# NXMaus.net
KiCad netlist of a schematic drawn in EAGLE
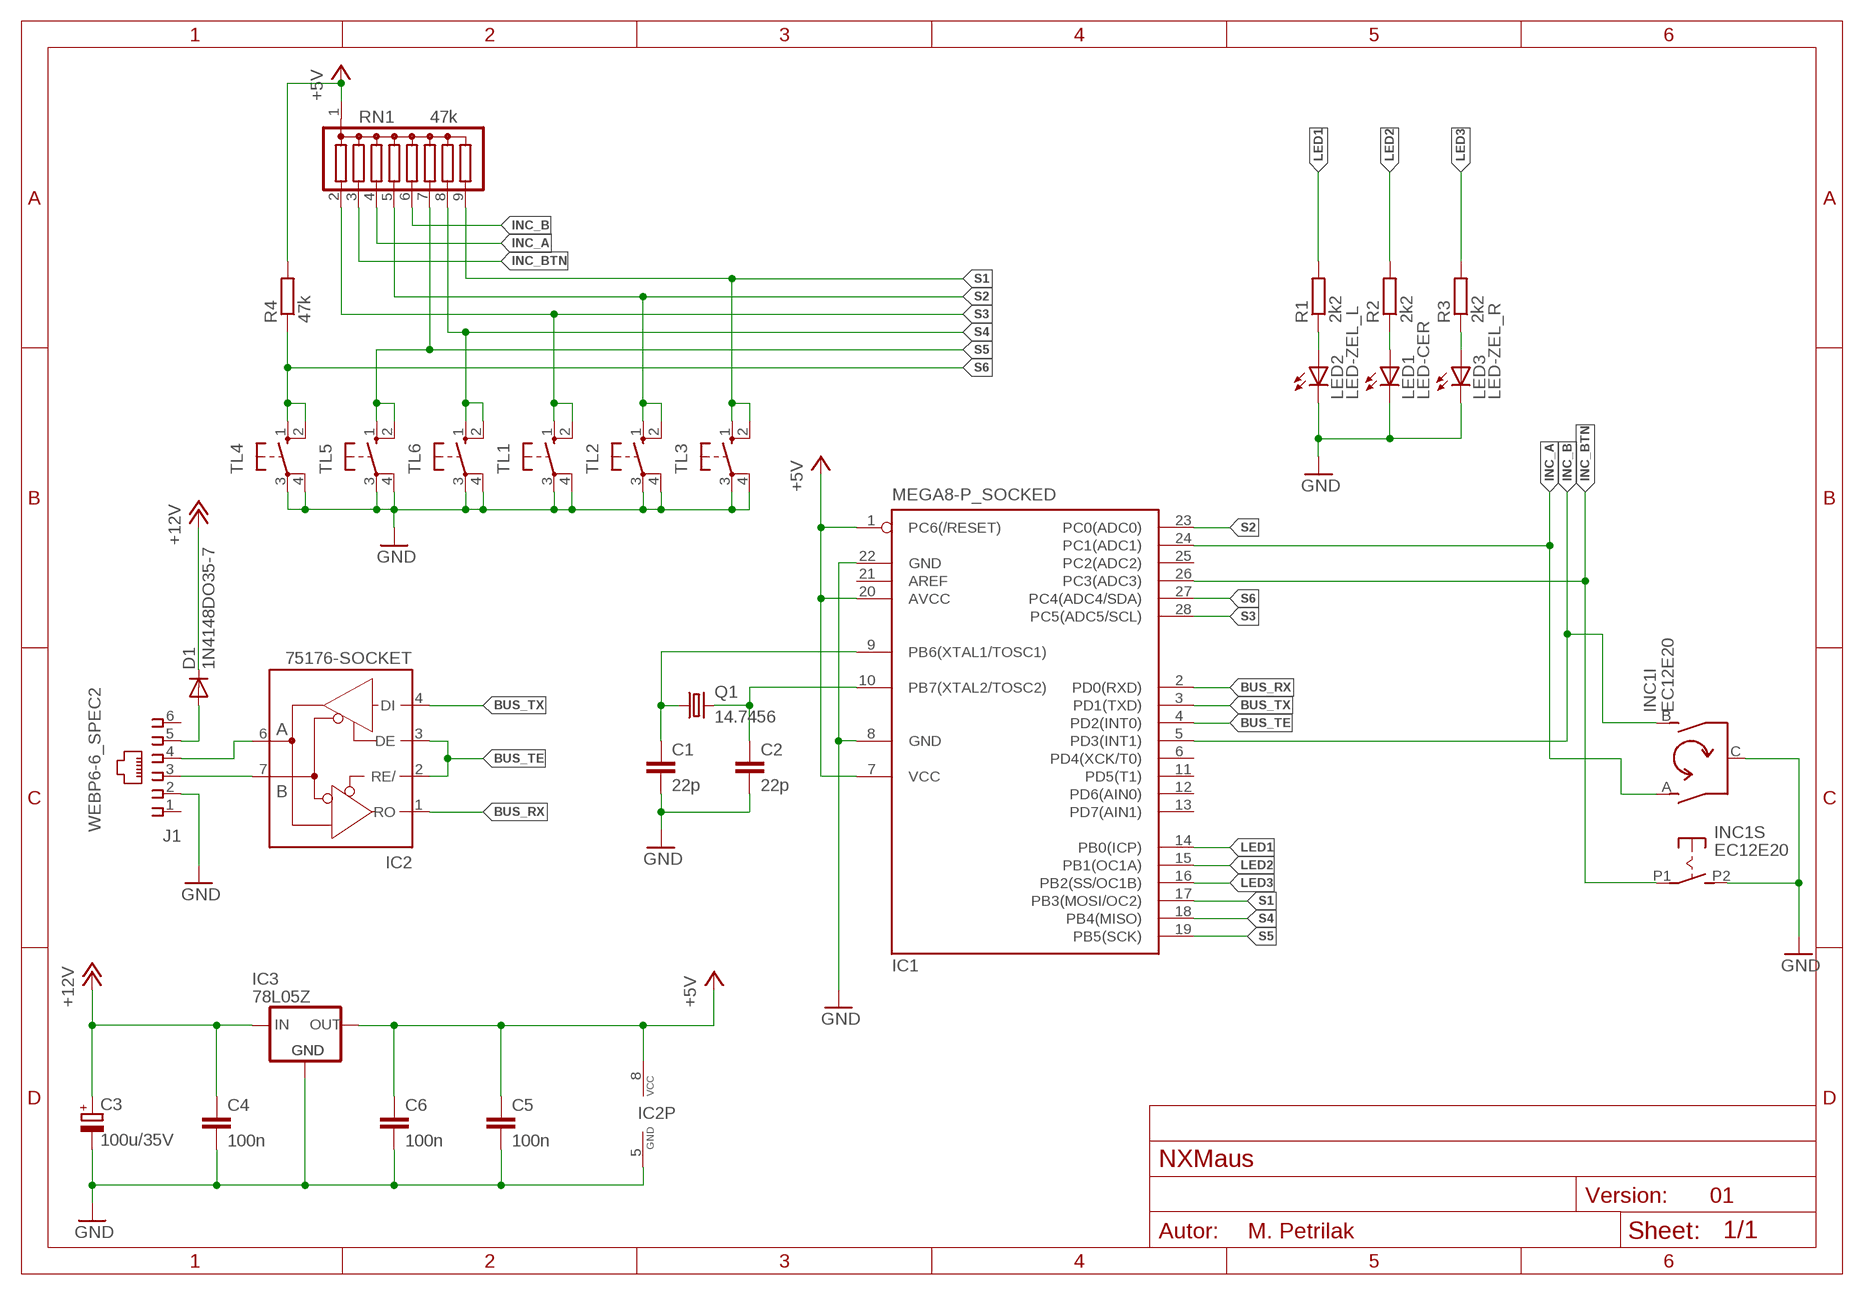
[diagram p0: schematic, sheet 1]

(export (version "E")
  (design (tool "Eeschema 10.0.6"))
  (components
    (comp (ref "C1")
      (value "22p")
      (footprint "eagle-import:C025_050-025X075")
      (libsource (lib "eagle-import") (part "C-EU025_050-025X075"))
    )
    (comp (ref "C2")
      (value "22p")
      (footprint "eagle-import:C025_050-025X075")
      (libsource (lib "eagle-import") (part "C-EU025_050-025X075"))
    )
    (comp (ref "C3")
      (value "100u/35V")
      (footprint "eagle-import:E2,5-6")
      (libsource (lib "eagle-import") (part "CPOL-EUE2.5-6"))
    )
    (comp (ref "C4")
      (value "100n")
      (footprint "eagle-import:C025_050-025X075")
      (libsource (lib "eagle-import") (part "C-EU025_050-025X075"))
    )
    (comp (ref "C5")
      (value "100n")
      (footprint "eagle-import:C025_050-025X075")
      (libsource (lib "eagle-import") (part "C-EU025_050-025X075"))
    )
    (comp (ref "C6")
      (value "100n")
      (footprint "eagle-import:C025_050-025X075")
      (libsource (lib "eagle-import") (part "C-EU025_050-025X075"))
    )
    (comp (ref "D1")
      (value "1N4148DO35-7")
      (footprint "eagle-import:DO35-7")
      (libsource (lib "eagle-import") (part "1N4148DO35-7"))
    )
    (comp (ref "IC1")
      (value "MEGA8-P_SOCKED")
      (footprint "eagle-import:SOKL-28U")
      (libsource (lib "eagle-import") (part "MEGA8-P_SOCKED"))
    )
    (comp (ref "IC2")
      (value "75176-SOCKET")
      (footprint "eagle-import:SOCKET-08")
      (libsource (lib "eagle-import") (part "75176-SOCKET"))
    )
    (comp (ref "IC3")
      (value "78L05Z")
      (footprint "eagle-import:TO92")
      (libsource (lib "eagle-import") (part "78ZL05"))
    )
    (comp (ref "INC1")
      (value "EC12E20")
      (footprint "eagle-import:EC12E20")
      (libsource (lib "eagle-import") (part "EC12E20"))
    )
    (comp (ref "J1")
      (value "WEBP6-6_SPEC2")
      (footprint "eagle-import:WEBP6-6_SPEC2")
      (libsource (lib "eagle-import") (part "WEBP6-6_SPEC2"))
    )
    (comp (ref "LED1")
      (value "LED-CER")
      (footprint "eagle-import:LED3MM")
      (libsource (lib "eagle-import") (part "LED3MM"))
    )
    (comp (ref "LED2")
      (value "LED-ZEL_L")
      (footprint "eagle-import:LED3MM")
      (libsource (lib "eagle-import") (part "LED3MM"))
    )
    (comp (ref "LED3")
      (value "LED-ZEL_R")
      (footprint "eagle-import:LED3MM")
      (libsource (lib "eagle-import") (part "LED3MM"))
    )
    (comp (ref "Q1")
      (value "14.7456")
      (footprint "eagle-import:HC49U70")
      (libsource (lib "eagle-import") (part "XTAL"))
    )
    (comp (ref "R1")
      (value "2k2")
      (footprint "eagle-import:0207_10")
      (libsource (lib "eagle-import") (part "R-EU_0207/10"))
    )
    (comp (ref "R2")
      (value "2k2")
      (footprint "eagle-import:0207_10")
      (libsource (lib "eagle-import") (part "R-EU_0207/10"))
    )
    (comp (ref "R3")
      (value "2k2")
      (footprint "eagle-import:0207_10")
      (libsource (lib "eagle-import") (part "R-EU_0207/10"))
    )
    (comp (ref "R4")
      (value "47k")
      (footprint "eagle-import:R1206")
      (libsource (lib "eagle-import") (part "R-EU_R1206"))
    )
    (comp (ref "RN1")
      (value "47k")
      (footprint "eagle-import:SIL9")
      (libsource (lib "eagle-import") (part "G08R"))
    )
    (comp (ref "TL1")
      (value "10-XX")
      (footprint "eagle-import:B3F-10XX")
      (libsource (lib "eagle-import") (part "10-XX"))
    )
    (comp (ref "TL2")
      (value "10-XX")
      (footprint "eagle-import:B3F-10XX")
      (libsource (lib "eagle-import") (part "10-XX"))
    )
    (comp (ref "TL3")
      (value "10-XX")
      (footprint "eagle-import:B3F-10XX")
      (libsource (lib "eagle-import") (part "10-XX"))
    )
    (comp (ref "TL4")
      (value "10-XX")
      (footprint "eagle-import:B3F-10XX")
      (libsource (lib "eagle-import") (part "10-XX"))
    )
    (comp (ref "TL5")
      (value "10-XX")
      (footprint "eagle-import:B3F-10XX")
      (libsource (lib "eagle-import") (part "10-XX"))
    )
    (comp (ref "TL6")
      (value "10-XX")
      (footprint "eagle-import:B3F-10XX")
      (libsource (lib "eagle-import") (part "10-XX"))
    )
  )
  (nets
    (net (code "1") (name "+5V") (class "Default")
      (node (ref "C5") (pin "1") (pinfunction "1_1") (pintype "passive"))
      (node (ref "C6") (pin "1") (pinfunction "1_1") (pintype "passive"))
      (node (ref "IC1") (pin "1") (pinfunction "PC6(/RESET)_1") (pintype "bidirectional"))
      (node (ref "IC1") (pin "20") (pinfunction "AVCC_20") (pintype "power_in"))
      (node (ref "IC1") (pin "7") (pinfunction "VCC_7") (pintype "power_in"))
      (node (ref "IC2") (pin "8") (pinfunction "VCC_8") (pintype "power_in"))
      (node (ref "IC3") (pin "1") (pinfunction "VO_1") (pintype "passive"))
      (node (ref "R4") (pin "2") (pinfunction "2_2") (pintype "passive"))
      (node (ref "RN1") (pin "1") (pinfunction "1_1") (pintype "passive"))
    )
    (net (code "2") (name "+12V") (class "Default")
      (node (ref "C3") (pin "+") (pinfunction "+_+") (pintype "passive"))
      (node (ref "C4") (pin "1") (pinfunction "1_1") (pintype "passive"))
      (node (ref "D1") (pin "C") (pinfunction "C_C") (pintype "passive"))
      (node (ref "IC3") (pin "3") (pinfunction "VI_3") (pintype "input"))
    )
    (net (code "3") (name "BUS_RX") (class "Default")
      (node (ref "IC1") (pin "2") (pinfunction "PD0(RXD)_2") (pintype "bidirectional"))
      (node (ref "IC2") (pin "1") (pinfunction "RO_1") (pintype "output"))
    )
    (net (code "4") (name "BUS_TE") (class "Default")
      (node (ref "IC1") (pin "4") (pinfunction "PD2(INT0)_4") (pintype "bidirectional"))
      (node (ref "IC2") (pin "2") (pinfunction "RE/_2") (pintype "input"))
      (node (ref "IC2") (pin "3") (pinfunction "DE_3") (pintype "input"))
    )
    (net (code "5") (name "BUS_TX") (class "Default")
      (node (ref "IC1") (pin "3") (pinfunction "PD1(TXD)_3") (pintype "bidirectional"))
      (node (ref "IC2") (pin "4") (pinfunction "DI_4") (pintype "input"))
    )
    (net (code "6") (name "GND") (class "Default")
      (node (ref "C1") (pin "2") (pinfunction "2_2") (pintype "passive"))
      (node (ref "C1") (pin "3") (pinfunction "2_3") (pintype "passive"))
      (node (ref "C2") (pin "2") (pinfunction "2_2") (pintype "passive"))
      (node (ref "C2") (pin "3") (pinfunction "2_3") (pintype "passive"))
      (node (ref "C3") (pin "-") (pinfunction "-_-") (pintype "passive"))
      (node (ref "C4") (pin "2") (pinfunction "2_2") (pintype "passive"))
      (node (ref "C4") (pin "3") (pinfunction "2_3") (pintype "passive"))
      (node (ref "C5") (pin "2") (pinfunction "2_2") (pintype "passive"))
      (node (ref "C5") (pin "3") (pinfunction "2_3") (pintype "passive"))
      (node (ref "C6") (pin "2") (pinfunction "2_2") (pintype "passive"))
      (node (ref "C6") (pin "3") (pinfunction "2_3") (pintype "passive"))
      (node (ref "IC1") (pin "22") (pinfunction "GND_22") (pintype "power_in"))
      (node (ref "IC1") (pin "8") (pinfunction "GND_8") (pintype "power_in"))
      (node (ref "IC2") (pin "5") (pinfunction "GND_5") (pintype "power_in"))
      (node (ref "IC3") (pin "2") (pinfunction "GND_2") (pintype "passive"))
      (node (ref "INC1") (pin "C") (pinfunction "C_C") (pintype "passive"))
      (node (ref "INC1") (pin "P2") (pinfunction "S_P2") (pintype "passive"))
      (node (ref "J1") (pin "2") (pinfunction "2_2") (pintype "passive"))
      (node (ref "LED1") (pin "K") (pinfunction "C_K") (pintype "passive"))
      (node (ref "LED2") (pin "K") (pinfunction "C_K") (pintype "passive"))
      (node (ref "LED3") (pin "K") (pinfunction "C_K") (pintype "passive"))
      (node (ref "TL1") (pin "3") (pinfunction "P_3") (pintype "passive"))
      (node (ref "TL1") (pin "4") (pinfunction "P1_4") (pintype "passive"))
      (node (ref "TL2") (pin "3") (pinfunction "P_3") (pintype "passive"))
      (node (ref "TL2") (pin "4") (pinfunction "P1_4") (pintype "passive"))
      (node (ref "TL3") (pin "3") (pinfunction "P_3") (pintype "passive"))
      (node (ref "TL3") (pin "4") (pinfunction "P1_4") (pintype "passive"))
      (node (ref "TL4") (pin "3") (pinfunction "P_3") (pintype "passive"))
      (node (ref "TL4") (pin "4") (pinfunction "P1_4") (pintype "passive"))
      (node (ref "TL5") (pin "3") (pinfunction "P_3") (pintype "passive"))
      (node (ref "TL5") (pin "4") (pinfunction "P1_4") (pintype "passive"))
      (node (ref "TL6") (pin "3") (pinfunction "P_3") (pintype "passive"))
      (node (ref "TL6") (pin "4") (pinfunction "P1_4") (pintype "passive"))
    )
    (net (code "7") (name "INC_A") (class "Default")
      (node (ref "IC1") (pin "24") (pinfunction "PC1(ADC1)_24") (pintype "bidirectional"))
      (node (ref "INC1") (pin "A") (pinfunction "A_A") (pintype "passive"))
      (node (ref "RN1") (pin "4") (pinfunction "4_4") (pintype "passive"))
    )
    (net (code "8") (name "INC_B") (class "Default")
      (node (ref "IC1") (pin "5") (pinfunction "PD3(INT1)_5") (pintype "bidirectional"))
      (node (ref "INC1") (pin "B") (pinfunction "B_B") (pintype "passive"))
      (node (ref "RN1") (pin "6") (pinfunction "6_6") (pintype "passive"))
    )
    (net (code "9") (name "INC_BTN") (class "Default")
      (node (ref "IC1") (pin "26") (pinfunction "PC3(ADC3)_26") (pintype "bidirectional"))
      (node (ref "INC1") (pin "P1") (pinfunction "P_P1") (pintype "passive"))
      (node (ref "RN1") (pin "3") (pinfunction "3_3") (pintype "passive"))
    )
    (net (code "10") (name "LED1") (class "Default")
      (node (ref "IC1") (pin "14") (pinfunction "PB0(ICP)_14") (pintype "bidirectional"))
      (node (ref "R1") (pin "2") (pinfunction "2_2") (pintype "passive"))
    )
    (net (code "11") (name "LED2") (class "Default")
      (node (ref "IC1") (pin "15") (pinfunction "PB1(OC1A)_15") (pintype "bidirectional"))
      (node (ref "R2") (pin "2") (pinfunction "2_2") (pintype "passive"))
    )
    (net (code "12") (name "LED3") (class "Default")
      (node (ref "IC1") (pin "16") (pinfunction "PB2(SS/OC1B)_16") (pintype "bidirectional"))
      (node (ref "R3") (pin "2") (pinfunction "2_2") (pintype "passive"))
    )
    (net (code "13") (name "Net-(D1-PadA)") (class "Default")
      (node (ref "D1") (pin "A") (pinfunction "A_A") (pintype "passive"))
      (node (ref "J1") (pin "5") (pinfunction "5_5") (pintype "passive"))
    )
    (net (code "14") (name "Net-(IC1-PB6(XTAL1{slash}TOSC1))") (class "Default")
      (node (ref "C1") (pin "1") (pinfunction "1_1") (pintype "passive"))
      (node (ref "IC1") (pin "9") (pinfunction "PB6(XTAL1/TOSC1)_9") (pintype "bidirectional"))
      (node (ref "Q1") (pin "1") (pinfunction "1_1") (pintype "passive"))
    )
    (net (code "15") (name "Net-(IC1-PB7(XTAL2{slash}TOSC2))") (class "Default")
      (node (ref "C2") (pin "1") (pinfunction "1_1") (pintype "passive"))
      (node (ref "IC1") (pin "10") (pinfunction "PB7(XTAL2/TOSC2)_10") (pintype "bidirectional"))
      (node (ref "Q1") (pin "2") (pinfunction "2_2") (pintype "passive"))
    )
    (net (code "16") (name "Net-(IC2A-A)") (class "Default")
      (node (ref "IC2") (pin "6") (pinfunction "A_6") (pintype "passive"))
      (node (ref "J1") (pin "4") (pinfunction "4_4") (pintype "passive"))
    )
    (net (code "17") (name "Net-(IC2A-B)") (class "Default")
      (node (ref "IC2") (pin "7") (pinfunction "B_7") (pintype "passive"))
      (node (ref "J1") (pin "3") (pinfunction "3_3") (pintype "passive"))
    )
    (net (code "18") (name "Net-(LED1-PadA)") (class "Default")
      (node (ref "LED1") (pin "A") (pinfunction "A_A") (pintype "passive"))
      (node (ref "R2") (pin "1") (pinfunction "1_1") (pintype "passive"))
    )
    (net (code "19") (name "Net-(LED2-PadA)") (class "Default")
      (node (ref "LED2") (pin "A") (pinfunction "A_A") (pintype "passive"))
      (node (ref "R1") (pin "1") (pinfunction "1_1") (pintype "passive"))
    )
    (net (code "20") (name "Net-(LED3-PadA)") (class "Default")
      (node (ref "LED3") (pin "A") (pinfunction "A_A") (pintype "passive"))
      (node (ref "R3") (pin "1") (pinfunction "1_1") (pintype "passive"))
    )
    (net (code "21") (name "S1") (class "Default")
      (node (ref "IC1") (pin "17") (pinfunction "PB3(MOSI/OC2)_17") (pintype "bidirectional"))
      (node (ref "RN1") (pin "9") (pinfunction "9_9") (pintype "passive"))
      (node (ref "TL3") (pin "1") (pinfunction "S_1") (pintype "passive"))
      (node (ref "TL3") (pin "2") (pinfunction "S1_2") (pintype "passive"))
    )
    (net (code "22") (name "S2") (class "Default")
      (node (ref "IC1") (pin "23") (pinfunction "PC0(ADC0)_23") (pintype "bidirectional"))
      (node (ref "RN1") (pin "5") (pinfunction "5_5") (pintype "passive"))
      (node (ref "TL2") (pin "1") (pinfunction "S_1") (pintype "passive"))
      (node (ref "TL2") (pin "2") (pinfunction "S1_2") (pintype "passive"))
    )
    (net (code "23") (name "S3") (class "Default")
      (node (ref "IC1") (pin "28") (pinfunction "PC5(ADC5/SCL)_28") (pintype "bidirectional"))
      (node (ref "RN1") (pin "2") (pinfunction "2_2") (pintype "passive"))
      (node (ref "TL1") (pin "1") (pinfunction "S_1") (pintype "passive"))
      (node (ref "TL1") (pin "2") (pinfunction "S1_2") (pintype "passive"))
    )
    (net (code "24") (name "S4") (class "Default")
      (node (ref "IC1") (pin "18") (pinfunction "PB4(MISO)_18") (pintype "bidirectional"))
      (node (ref "RN1") (pin "8") (pinfunction "8_8") (pintype "passive"))
      (node (ref "TL6") (pin "1") (pinfunction "S_1") (pintype "passive"))
      (node (ref "TL6") (pin "2") (pinfunction "S1_2") (pintype "passive"))
    )
    (net (code "25") (name "S5") (class "Default")
      (node (ref "IC1") (pin "19") (pinfunction "PB5(SCK)_19") (pintype "bidirectional"))
      (node (ref "RN1") (pin "7") (pinfunction "7_7") (pintype "passive"))
      (node (ref "TL5") (pin "1") (pinfunction "S_1") (pintype "passive"))
      (node (ref "TL5") (pin "2") (pinfunction "S1_2") (pintype "passive"))
    )
    (net (code "26") (name "S6") (class "Default")
      (node (ref "IC1") (pin "27") (pinfunction "PC4(ADC4/SDA)_27") (pintype "bidirectional"))
      (node (ref "R4") (pin "1") (pinfunction "1_1") (pintype "passive"))
      (node (ref "TL4") (pin "1") (pinfunction "S_1") (pintype "passive"))
      (node (ref "TL4") (pin "2") (pinfunction "S1_2") (pintype "passive"))
    )
    (net (code "27") (name "unconnected-(IC1-AREF-Pad21)") (class "Default")
      (node (ref "IC1") (pin "21") (pinfunction "AREF_21") (pintype "passive"))
    )
    (net (code "28") (name "unconnected-(IC1-PC2(ADC2)-Pad25)") (class "Default")
      (node (ref "IC1") (pin "25") (pinfunction "PC2(ADC2)_25") (pintype "bidirectional"))
    )
    (net (code "29") (name "unconnected-(IC1-PD4(XCK{slash}T0)-Pad6)") (class "Default")
      (node (ref "IC1") (pin "6") (pinfunction "PD4(XCK/T0)_6") (pintype "bidirectional"))
    )
    (net (code "30") (name "unconnected-(IC1-PD5(T1)-Pad11)") (class "Default")
      (node (ref "IC1") (pin "11") (pinfunction "PD5(T1)_11") (pintype "bidirectional"))
    )
    (net (code "31") (name "unconnected-(IC1-PD6(AIN0)-Pad12)") (class "Default")
      (node (ref "IC1") (pin "12") (pinfunction "PD6(AIN0)_12") (pintype "bidirectional"))
    )
    (net (code "32") (name "unconnected-(IC1-PD7(AIN1)-Pad13)") (class "Default")
      (node (ref "IC1") (pin "13") (pinfunction "PD7(AIN1)_13") (pintype "bidirectional"))
    )
    (net (code "33") (name "unconnected-(J1-Pad1)") (class "Default")
      (node (ref "J1") (pin "1") (pinfunction "1_1") (pintype "passive"))
    )
    (net (code "34") (name "unconnected-(J1-Pad6)") (class "Default")
      (node (ref "J1") (pin "6") (pinfunction "6_6") (pintype "passive"))
    )
  )
)
